# LowLevelv2.net
KiCad netlist of a schematic drawn in EAGLE
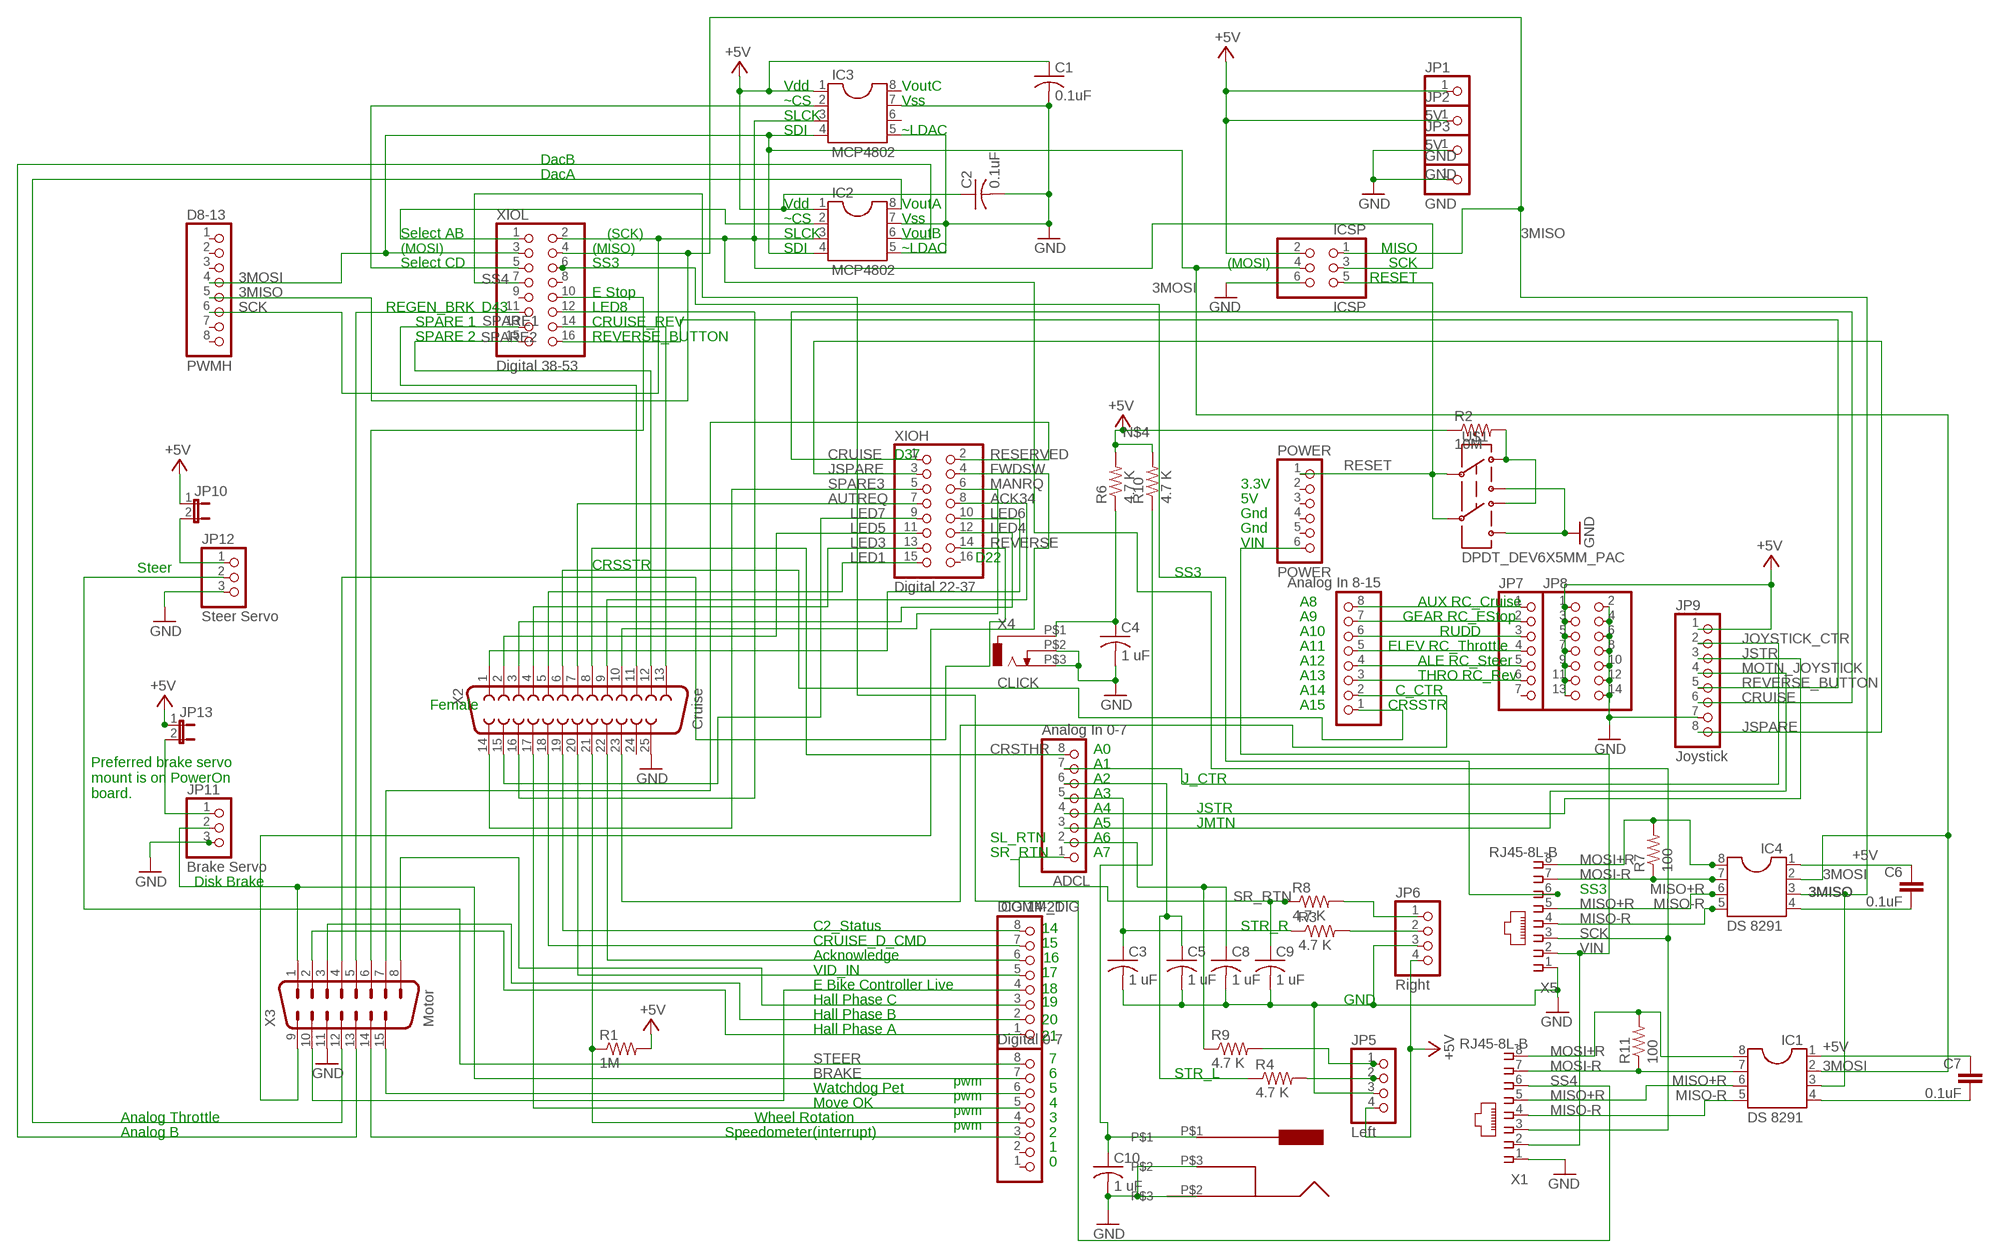
[diagram p0: schematic, sheet 1]

(export (version "E")
  (design (tool "Eeschema 10.0.6"))
  (components
    (comp (ref "ADCH")
      (value "Analog In 8-15")
      (footprint "eagle-import:1X08")
      (libsource (lib "eagle-import") (part "PINHD-1X8"))
    )
    (comp (ref "ADCL")
      (value "Analog In 0-7")
      (footprint "eagle-import:1X08")
      (libsource (lib "eagle-import") (part "PINHD-1X8"))
    )
    (comp (ref "C1")
      (value "0.1uF")
      (footprint "eagle-import:C025-025X050")
      (libsource (lib "eagle-import") (part "C-US025-025X050"))
    )
    (comp (ref "C2")
      (value "0.1uF")
      (footprint "eagle-import:C025-025X050")
      (libsource (lib "eagle-import") (part "C-US025-025X050"))
    )
    (comp (ref "C3")
      (value "1 uF")
      (footprint "eagle-import:C025-030X050")
      (libsource (lib "eagle-import") (part "C-US025-030X050"))
    )
    (comp (ref "C4")
      (value "1 uF")
      (footprint "eagle-import:C025-030X050")
      (libsource (lib "eagle-import") (part "C-US025-030X050"))
    )
    (comp (ref "C5")
      (value "1 uF")
      (footprint "eagle-import:C025-030X050")
      (libsource (lib "eagle-import") (part "C-US025-030X050"))
    )
    (comp (ref "C6")
      (value "0.1uF")
      (footprint "eagle-import:C2.5-2")
      (libsource (lib "eagle-import") (part "C2.5/2"))
    )
    (comp (ref "C7")
      (value "0.1uF")
      (footprint "eagle-import:C2.5-2")
      (libsource (lib "eagle-import") (part "C2.5/2"))
    )
    (comp (ref "C8")
      (value "1 uF")
      (footprint "eagle-import:C025-030X050")
      (libsource (lib "eagle-import") (part "C-US025-030X050"))
    )
    (comp (ref "C9")
      (value "1 uF")
      (footprint "eagle-import:C025-030X050")
      (libsource (lib "eagle-import") (part "C-US025-030X050"))
    )
    (comp (ref "C10")
      (value "1 uF")
      (footprint "eagle-import:C025-030X050")
      (libsource (lib "eagle-import") (part "C-US025-030X050"))
    )
    (comp (ref "COMM_DIG")
      (value "DIG 14-21")
      (footprint "eagle-import:1X08")
      (libsource (lib "eagle-import") (part "PINHD-1X8"))
    )
    (comp (ref "D8-13")
      (value "PWMH")
      (footprint "eagle-import:1X08")
      (libsource (lib "eagle-import") (part "PINHD-1X8"))
    )
    (comp (ref "GND")
      (value "GND")
      (footprint "eagle-import:1X01")
      (libsource (lib "eagle-import") (part "PINHD-1X1"))
    )
    (comp (ref "IC1")
      (value "DS 8291")
      (footprint "eagle-import:DIL08")
      (libsource (lib "eagle-import") (part "DIL8"))
    )
    (comp (ref "IC2")
      (value "MCP4802")
      (footprint "eagle-import:DIL08")
      (libsource (lib "eagle-import") (part "DIL8"))
    )
    (comp (ref "IC3")
      (value "MCP4802")
      (footprint "eagle-import:DIL08")
      (libsource (lib "eagle-import") (part "DIL8"))
    )
    (comp (ref "IC4")
      (value "DS 8291")
      (footprint "eagle-import:DIL08")
      (libsource (lib "eagle-import") (part "DIL8"))
    )
    (comp (ref "ICSP")
      (value "ICSP")
      (footprint "eagle-import:2X03")
      (libsource (lib "eagle-import") (part "PINHD-2X3"))
    )
    (comp (ref "JP1")
      (value "5V")
      (footprint "eagle-import:1X01")
      (libsource (lib "eagle-import") (part "PINHD-1X1"))
    )
    (comp (ref "JP2")
      (value "5V")
      (footprint "eagle-import:1X01")
      (libsource (lib "eagle-import") (part "PINHD-1X1"))
    )
    (comp (ref "JP3")
      (value "GND")
      (footprint "eagle-import:1X01")
      (libsource (lib "eagle-import") (part "PINHD-1X1"))
    )
    (comp (ref "JP5")
      (value "Left")
      (footprint "eagle-import:1X04_90")
      (libsource (lib "eagle-import") (part "PINHD-1X4/90"))
    )
    (comp (ref "JP6")
      (value "Right")
      (footprint "eagle-import:1X04_90")
      (libsource (lib "eagle-import") (part "PINHD-1X4/90"))
    )
    (comp (ref "JP7")
      (value "PINHD-1X7")
      (footprint "eagle-import:1X07")
      (libsource (lib "eagle-import") (part "PINHD-1X7"))
    )
    (comp (ref "JP8")
      (value "PINHD-2X7")
      (footprint "eagle-import:2X07")
      (libsource (lib "eagle-import") (part "PINHD-2X7"))
    )
    (comp (ref "JP9")
      (value "Joystick")
      (footprint "eagle-import:1X08_90")
      (libsource (lib "eagle-import") (part "PINHD-1X8/90"))
    )
    (comp (ref "JP10")
      (value "JP1E")
      (footprint "eagle-import:JP1")
      (libsource (lib "eagle-import") (part "JP1E"))
    )
    (comp (ref "JP11")
      (value "Brake Servo")
      (footprint "eagle-import:1X03_90")
      (libsource (lib "eagle-import") (part "PINHD-1X3/90"))
    )
    (comp (ref "JP12")
      (value "Steer Servo")
      (footprint "eagle-import:1X03_90")
      (libsource (lib "eagle-import") (part "PINHD-1X3/90"))
    )
    (comp (ref "JP13")
      (value "JP1E")
      (footprint "eagle-import:JP1")
      (libsource (lib "eagle-import") (part "JP1E"))
    )
    (comp (ref "POWER")
      (value "POWER")
      (footprint "eagle-import:1X06")
      (libsource (lib "eagle-import") (part "PINHD-1X6"))
    )
    (comp (ref "PWML")
      (value "Digital 0-7")
      (footprint "eagle-import:1X08")
      (libsource (lib "eagle-import") (part "PINHD-1X8"))
    )
    (comp (ref "R1")
      (value "1M")
      (footprint "eagle-import:0207_10")
      (libsource (lib "eagle-import") (part "R-US_0207/10"))
    )
    (comp (ref "R2")
      (value "10M")
      (footprint "eagle-import:0207_10")
      (libsource (lib "eagle-import") (part "R-US_0207/10"))
    )
    (comp (ref "R3")
      (value "4.7 K")
      (footprint "eagle-import:0207_10")
      (libsource (lib "eagle-import") (part "R-US_0207/10"))
    )
    (comp (ref "R4")
      (value "4.7 K")
      (footprint "eagle-import:0207_10")
      (libsource (lib "eagle-import") (part "R-US_0207/10"))
    )
    (comp (ref "R6")
      (value "4.7 K")
      (footprint "eagle-import:0207_10")
      (libsource (lib "eagle-import") (part "R-US_0207/10"))
    )
    (comp (ref "R7")
      (value "100")
      (footprint "eagle-import:0207_10")
      (libsource (lib "eagle-import") (part "R-US_0207/10"))
    )
    (comp (ref "R8")
      (value "4.7 K")
      (footprint "eagle-import:0207_10")
      (libsource (lib "eagle-import") (part "R-US_0207/10"))
    )
    (comp (ref "R9")
      (value "4.7 K")
      (footprint "eagle-import:0207_10")
      (libsource (lib "eagle-import") (part "R-US_0207/10"))
    )
    (comp (ref "R10")
      (value "4.7 K")
      (footprint "eagle-import:0207_10")
      (libsource (lib "eagle-import") (part "R-US_0207/10"))
    )
    (comp (ref "R11")
      (value "100")
      (footprint "eagle-import:0207_10")
      (libsource (lib "eagle-import") (part "R-US_0207/10"))
    )
    (comp (ref "U$1")
      (value "DPDT_DEV6X5MM_PAC")
      (footprint "eagle-import:NEWSWITCH2_PAC")
      (libsource (lib "eagle-import") (part "DPDT_DEV6X5MM_PAC"))
    )
    (comp (ref "U$2")
      (value "CUI_JACKTHROUGH_HOLE")
      (footprint "eagle-import:CUIJACK")
      (libsource (lib "eagle-import") (part "CUI_JACKTHROUGH_HOLE"))
    )
    (comp (ref "X1")
      (value "RJ45-8L-B")
      (footprint "eagle-import:RJ45-NO-SHIELD")
      (fields (field (name "MF") "TYCO ELECTRONICS"))
      (libsource (lib "eagle-import") (part "RJ45-8L-B"))
    )
    (comp (ref "X2")
      (value "Cruise")
      (footprint "eagle-import:F25H")
      (libsource (lib "eagle-import") (part "F25H"))
    )
    (comp (ref "X3")
      (value "Motor")
      (footprint "eagle-import:182-015-MALE")
      (libsource (lib "eagle-import") (part "M15-182"))
    )
    (comp (ref "X4")
      (value "CLICK")
      (footprint "eagle-import:ODO_JACK")
      (libsource (lib "eagle-import") (part "ODO_JACK"))
    )
    (comp (ref "X5")
      (value "RJ45-8L-B")
      (footprint "eagle-import:RJ45-NO-SHIELD")
      (fields (field (name "MF") "TYCO ELECTRONICS"))
      (libsource (lib "eagle-import") (part "RJ45-8L-B"))
    )
    (comp (ref "XIOH")
      (value "Digital 22-37")
      (footprint "eagle-import:2X08")
      (libsource (lib "eagle-import") (part "PINHD-2X8"))
    )
    (comp (ref "XIOL")
      (value "Digital 38-53")
      (footprint "eagle-import:2X08")
      (libsource (lib "eagle-import") (part "PINHD-2X8"))
    )
  )
  (nets
    (net (code "1") (name "+5V") (class "Default")
      (node (ref "C1") (pin "1") (pinfunction "1_1") (pintype "passive"))
      (node (ref "C2") (pin "1") (pinfunction "1_1") (pintype "passive"))
      (node (ref "C6") (pin "1") (pinfunction "1_1") (pintype "passive"))
      (node (ref "IC2") (pin "1") (pinfunction "1_1") (pintype "passive"))
      (node (ref "IC3") (pin "1") (pinfunction "1_1") (pintype "passive"))
      (node (ref "IC4") (pin "1") (pinfunction "1_1") (pintype "passive"))
      (node (ref "ICSP") (pin "2") (pinfunction "2_2") (pintype "passive"))
      (node (ref "JP1") (pin "1") (pinfunction "1_1") (pintype "passive"))
      (node (ref "JP10") (pin "1") (pinfunction "1_1") (pintype "passive"))
      (node (ref "JP13") (pin "1") (pinfunction "1_1") (pintype "passive"))
      (node (ref "JP2") (pin "1") (pinfunction "1_1") (pintype "passive"))
      (node (ref "JP5") (pin "4") (pinfunction "4_4") (pintype "passive"))
      (node (ref "JP6") (pin "4") (pinfunction "4_4") (pintype "passive"))
      (node (ref "JP8") (pin "1") (pinfunction "1_1") (pintype "passive"))
      (node (ref "JP8") (pin "11") (pinfunction "11_11") (pintype "passive"))
      (node (ref "JP8") (pin "13") (pinfunction "13_13") (pintype "passive"))
      (node (ref "JP8") (pin "3") (pinfunction "3_3") (pintype "passive"))
      (node (ref "JP8") (pin "5") (pinfunction "5_5") (pintype "passive"))
      (node (ref "JP8") (pin "7") (pinfunction "7_7") (pintype "passive"))
      (node (ref "JP8") (pin "9") (pinfunction "9_9") (pintype "passive"))
      (node (ref "JP9") (pin "1") (pinfunction "1_1") (pintype "passive"))
      (node (ref "R1") (pin "2") (pinfunction "2_2") (pintype "passive"))
      (node (ref "R10") (pin "2") (pinfunction "2_2") (pintype "passive"))
      (node (ref "R2") (pin "1") (pinfunction "1_1") (pintype "passive"))
      (node (ref "R6") (pin "2") (pinfunction "2_2") (pintype "passive"))
    )
    (net (code "2") (name "3MISO") (class "Default")
      (node (ref "D8-13") (pin "5") (pinfunction "5_5") (pintype "passive"))
      (node (ref "IC1") (pin "3") (pinfunction "3_3") (pintype "passive"))
      (node (ref "IC4") (pin "3") (pinfunction "3_3") (pintype "passive"))
      (node (ref "ICSP") (pin "1") (pinfunction "1_1") (pintype "passive"))
      (node (ref "XIOL") (pin "4") (pinfunction "4_4") (pintype "passive"))
    )
    (net (code "3") (name "3MOSI") (class "Default")
      (node (ref "D8-13") (pin "4") (pinfunction "4_4") (pintype "passive"))
      (node (ref "IC1") (pin "2") (pinfunction "2_2") (pintype "passive"))
      (node (ref "IC2") (pin "4") (pinfunction "4_4") (pintype "passive"))
      (node (ref "IC3") (pin "4") (pinfunction "4_4") (pintype "passive"))
      (node (ref "IC4") (pin "2") (pinfunction "2_2") (pintype "passive"))
      (node (ref "ICSP") (pin "4") (pinfunction "4_4") (pintype "passive"))
      (node (ref "XIOL") (pin "3") (pinfunction "3_3") (pintype "passive"))
    )
    (net (code "4") (name "ACK34") (class "Default")
      (node (ref "X2") (pin "9") (pinfunction "9_9") (pintype "passive"))
      (node (ref "XIOH") (pin "8") (pinfunction "8_8") (pintype "passive"))
    )
    (net (code "5") (name "AUTREQ") (class "Default")
      (node (ref "X2") (pin "7") (pinfunction "7_7") (pintype "passive"))
      (node (ref "XIOH") (pin "7") (pinfunction "7_7") (pintype "passive"))
    )
    (net (code "6") (name "BRAKE") (class "Default")
      (node (ref "JP11") (pin "2") (pinfunction "2_2") (pintype "passive"))
      (node (ref "PWML") (pin "7") (pinfunction "7_7") (pintype "passive"))
      (node (ref "X3") (pin "1") (pinfunction "1_1") (pintype "passive"))
    )
    (net (code "7") (name "CRSTHR") (class "Default")
      (node (ref "ADCL") (pin "8") (pinfunction "8_8") (pintype "passive"))
      (node (ref "X2") (pin "8") (pinfunction "8_8") (pintype "passive"))
    )
    (net (code "8") (name "CRUISE") (class "Default")
      (node (ref "JP9") (pin "6") (pinfunction "6_6") (pintype "passive"))
      (node (ref "XIOH") (pin "1") (pinfunction "1_1") (pintype "passive"))
    )
    (net (code "9") (name "CRUISE_D_CMD") (class "Default")
      (node (ref "COMM_DIG") (pin "7") (pinfunction "7_7") (pintype "passive"))
      (node (ref "X2") (pin "18") (pinfunction "18_18") (pintype "passive"))
    )
    (net (code "10") (name "CRUISE_REV") (class "Default")
      (node (ref "X2") (pin "13") (pinfunction "13_13") (pintype "passive"))
      (node (ref "XIOL") (pin "14") (pinfunction "14_14") (pintype "passive"))
    )
    (net (code "11") (name "FWDSW") (class "Default")
      (node (ref "X3") (pin "9") (pinfunction "9_9") (pintype "passive"))
      (node (ref "XIOH") (pin "4") (pinfunction "4_4") (pintype "passive"))
    )
    (net (code "12") (name "GND") (class "Default")
      (node (ref "C1") (pin "2") (pinfunction "2_2") (pintype "passive"))
      (node (ref "C10") (pin "2") (pinfunction "2_2") (pintype "passive"))
      (node (ref "C2") (pin "2") (pinfunction "2_2") (pintype "passive"))
      (node (ref "C3") (pin "2") (pinfunction "2_2") (pintype "passive"))
      (node (ref "C4") (pin "2") (pinfunction "2_2") (pintype "passive"))
      (node (ref "C5") (pin "2") (pinfunction "2_2") (pintype "passive"))
      (node (ref "C8") (pin "2") (pinfunction "2_2") (pintype "passive"))
      (node (ref "C9") (pin "2") (pinfunction "2_2") (pintype "passive"))
      (node (ref "GND") (pin "1") (pinfunction "1_1") (pintype "passive"))
      (node (ref "IC2") (pin "5") (pinfunction "5_5") (pintype "passive"))
      (node (ref "IC2") (pin "7") (pinfunction "7_7") (pintype "passive"))
      (node (ref "IC3") (pin "5") (pinfunction "5_5") (pintype "passive"))
      (node (ref "IC3") (pin "7") (pinfunction "7_7") (pintype "passive"))
      (node (ref "ICSP") (pin "6") (pinfunction "6_6") (pintype "passive"))
      (node (ref "JP11") (pin "3") (pinfunction "3_3") (pintype "passive"))
      (node (ref "JP12") (pin "3") (pinfunction "3_3") (pintype "passive"))
      (node (ref "JP3") (pin "1") (pinfunction "1_1") (pintype "passive"))
      (node (ref "JP5") (pin "3") (pinfunction "3_3") (pintype "passive"))
      (node (ref "JP6") (pin "3") (pinfunction "3_3") (pintype "passive"))
      (node (ref "JP8") (pin "10") (pinfunction "10_10") (pintype "passive"))
      (node (ref "JP8") (pin "12") (pinfunction "12_12") (pintype "passive"))
      (node (ref "JP8") (pin "14") (pinfunction "14_14") (pintype "passive"))
      (node (ref "JP8") (pin "2") (pinfunction "2_2") (pintype "passive"))
      (node (ref "JP8") (pin "4") (pinfunction "4_4") (pintype "passive"))
      (node (ref "JP8") (pin "6") (pinfunction "6_6") (pintype "passive"))
      (node (ref "JP8") (pin "8") (pinfunction "8_8") (pintype "passive"))
      (node (ref "JP9") (pin "7") (pinfunction "7_7") (pintype "passive"))
      (node (ref "U$1") (pin "PIN3") (pinfunction "3_PIN3") (pintype "bidirectional"))
      (node (ref "U$1") (pin "PIN6") (pinfunction "6_PIN6") (pintype "bidirectional"))
      (node (ref "U$2") (pin "P$2") (pinfunction "P$3_P$2") (pintype "bidirectional"))
      (node (ref "U$2") (pin "P$3") (pinfunction "P$2_P$3") (pintype "bidirectional"))
      (node (ref "X1") (pin "1") (pinfunction "1_1") (pintype "passive"))
      (node (ref "X2") (pin "25") (pinfunction "25_25") (pintype "passive"))
      (node (ref "X3") (pin "11") (pinfunction "11_11") (pintype "passive"))
      (node (ref "X4") (pin "P$2") (pinfunction "2_P$2") (pintype "passive"))
      (node (ref "X4") (pin "P$3") (pinfunction "3_P$3") (pintype "passive"))
      (node (ref "X5") (pin "1") (pinfunction "1_1") (pintype "passive"))
    )
    (net (code "13") (name "JOYSTICK_CTR") (class "Default")
      (node (ref "ADCL") (pin "7") (pinfunction "7_7") (pintype "passive"))
      (node (ref "JP9") (pin "2") (pinfunction "2_2") (pintype "passive"))
    )
    (net (code "14") (name "JSPARE") (class "Default")
      (node (ref "JP9") (pin "8") (pinfunction "8_8") (pintype "passive"))
      (node (ref "XIOH") (pin "3") (pinfunction "3_3") (pintype "passive"))
    )
    (net (code "15") (name "JSTR") (class "Default")
      (node (ref "ADCL") (pin "4") (pinfunction "4_4") (pintype "passive"))
      (node (ref "JP9") (pin "3") (pinfunction "3_3") (pintype "passive"))
    )
    (net (code "16") (name "LED1") (class "Default")
      (node (ref "X2") (pin "5") (pinfunction "5_5") (pintype "passive"))
      (node (ref "XIOH") (pin "15") (pinfunction "15_15") (pintype "passive"))
    )
    (net (code "17") (name "LED3") (class "Default")
      (node (ref "X2") (pin "4") (pinfunction "4_4") (pintype "passive"))
      (node (ref "XIOH") (pin "13") (pinfunction "13_13") (pintype "passive"))
    )
    (net (code "18") (name "LED4") (class "Default")
      (node (ref "X2") (pin "3") (pinfunction "3_3") (pintype "passive"))
      (node (ref "XIOH") (pin "12") (pinfunction "12_12") (pintype "passive"))
    )
    (net (code "19") (name "LED5") (class "Default")
      (node (ref "X2") (pin "2") (pinfunction "2_2") (pintype "passive"))
      (node (ref "XIOH") (pin "11") (pinfunction "11_11") (pintype "passive"))
    )
    (net (code "20") (name "LED6") (class "Default")
      (node (ref "X2") (pin "1") (pinfunction "1_1") (pintype "passive"))
      (node (ref "XIOH") (pin "10") (pinfunction "10_10") (pintype "passive"))
    )
    (net (code "21") (name "LED7") (class "Default")
      (node (ref "X2") (pin "15") (pinfunction "15_15") (pintype "passive"))
      (node (ref "XIOH") (pin "9") (pinfunction "9_9") (pintype "passive"))
    )
    (net (code "22") (name "LED8") (class "Default")
      (node (ref "X2") (pin "16") (pinfunction "16_16") (pintype "passive"))
      (node (ref "XIOL") (pin "12") (pinfunction "12_12") (pintype "passive"))
    )
    (net (code "23") (name "MANRQ") (class "Default")
      (node (ref "X2") (pin "10") (pinfunction "10_10") (pintype "passive"))
      (node (ref "XIOH") (pin "6") (pinfunction "6_6") (pintype "passive"))
    )
    (net (code "24") (name "MISO+R") (class "Default")
      (node (ref "IC1") (pin "6") (pinfunction "6_6") (pintype "passive"))
      (node (ref "IC4") (pin "6") (pinfunction "6_6") (pintype "passive"))
      (node (ref "X1") (pin "5") (pinfunction "5_5") (pintype "passive"))
      (node (ref "X5") (pin "5") (pinfunction "5_5") (pintype "passive"))
    )
    (net (code "25") (name "MISO-R") (class "Default")
      (node (ref "IC1") (pin "5") (pinfunction "5_5") (pintype "passive"))
      (node (ref "IC4") (pin "5") (pinfunction "5_5") (pintype "passive"))
      (node (ref "X1") (pin "4") (pinfunction "4_4") (pintype "passive"))
      (node (ref "X5") (pin "4") (pinfunction "4_4") (pintype "passive"))
    )
    (net (code "26") (name "MOSI+R") (class "Default")
      (node (ref "IC1") (pin "8") (pinfunction "8_8") (pintype "passive"))
      (node (ref "IC4") (pin "8") (pinfunction "8_8") (pintype "passive"))
      (node (ref "R11") (pin "2") (pinfunction "2_2") (pintype "passive"))
      (node (ref "R7") (pin "2") (pinfunction "2_2") (pintype "passive"))
      (node (ref "X1") (pin "8") (pinfunction "8_8") (pintype "passive"))
      (node (ref "X5") (pin "8") (pinfunction "8_8") (pintype "passive"))
    )
    (net (code "27") (name "MOSI-R") (class "Default")
      (node (ref "IC1") (pin "7") (pinfunction "7_7") (pintype "passive"))
      (node (ref "IC4") (pin "7") (pinfunction "7_7") (pintype "passive"))
      (node (ref "R11") (pin "1") (pinfunction "1_1") (pintype "passive"))
      (node (ref "R7") (pin "1") (pinfunction "1_1") (pintype "passive"))
      (node (ref "X1") (pin "7") (pinfunction "7_7") (pintype "passive"))
      (node (ref "X5") (pin "7") (pinfunction "7_7") (pintype "passive"))
    )
    (net (code "28") (name "MOTN_JOYSTICK") (class "Default")
      (node (ref "ADCL") (pin "3") (pinfunction "3_3") (pintype "passive"))
      (node (ref "JP9") (pin "4") (pinfunction "4_4") (pintype "passive"))
    )
    (net (code "29") (name "N$4") (class "Default")
      (node (ref "C4") (pin "1") (pinfunction "1_1") (pintype "passive"))
      (node (ref "R6") (pin "1") (pinfunction "1_1") (pintype "passive"))
      (node (ref "X4") (pin "P$1") (pinfunction "1_P$1") (pintype "passive"))
    )
    (net (code "30") (name "Net-(ADCH-Pad1)") (class "Default")
      (node (ref "ADCH") (pin "1") (pinfunction "1_1") (pintype "passive"))
      (node (ref "X2") (pin "6") (pinfunction "6_6") (pintype "passive"))
    )
    (net (code "31") (name "Net-(ADCH-Pad2)") (class "Default")
      (node (ref "ADCH") (pin "2") (pinfunction "2_2") (pintype "passive"))
      (node (ref "X2") (pin "23") (pinfunction "23_23") (pintype "passive"))
    )
    (net (code "32") (name "Net-(ADCH-Pad3)") (class "Default")
      (node (ref "ADCH") (pin "3") (pinfunction "3_3") (pintype "passive"))
      (node (ref "JP7") (pin "6") (pinfunction "6_6") (pintype "passive"))
    )
    (net (code "33") (name "Net-(ADCH-Pad4)") (class "Default")
      (node (ref "ADCH") (pin "4") (pinfunction "4_4") (pintype "passive"))
      (node (ref "JP7") (pin "5") (pinfunction "5_5") (pintype "passive"))
    )
    (net (code "34") (name "Net-(ADCH-Pad5)") (class "Default")
      (node (ref "ADCH") (pin "5") (pinfunction "5_5") (pintype "passive"))
      (node (ref "JP7") (pin "4") (pinfunction "4_4") (pintype "passive"))
    )
    (net (code "35") (name "Net-(ADCH-Pad6)") (class "Default")
      (node (ref "ADCH") (pin "6") (pinfunction "6_6") (pintype "passive"))
      (node (ref "JP7") (pin "3") (pinfunction "3_3") (pintype "passive"))
    )
    (net (code "36") (name "Net-(ADCH-Pad7)") (class "Default")
      (node (ref "ADCH") (pin "7") (pinfunction "7_7") (pintype "passive"))
      (node (ref "JP7") (pin "2") (pinfunction "2_2") (pintype "passive"))
    )
    (net (code "37") (name "Net-(ADCH-Pad8)") (class "Default")
      (node (ref "ADCH") (pin "8") (pinfunction "8_8") (pintype "passive"))
      (node (ref "JP7") (pin "1") (pinfunction "1_1") (pintype "passive"))
    )
    (net (code "38") (name "Net-(ADCL-Pad2)") (class "Default")
      (node (ref "ADCL") (pin "2") (pinfunction "2_2") (pintype "passive"))
      (node (ref "C8") (pin "1") (pinfunction "1_1") (pintype "passive"))
      (node (ref "R9") (pin "1") (pinfunction "1_1") (pintype "passive"))
    )
    (net (code "39") (name "Net-(ADCL-Pad5)") (class "Default")
      (node (ref "ADCL") (pin "5") (pinfunction "5_5") (pintype "passive"))
      (node (ref "C3") (pin "1") (pinfunction "1_1") (pintype "passive"))
      (node (ref "R3") (pin "1") (pinfunction "1_1") (pintype "passive"))
    )
    (net (code "40") (name "Net-(ADCL-Pad6)") (class "Default")
      (node (ref "ADCL") (pin "6") (pinfunction "6_6") (pintype "passive"))
      (node (ref "C5") (pin "1") (pinfunction "1_1") (pintype "passive"))
      (node (ref "R4") (pin "1") (pinfunction "1_1") (pintype "passive"))
    )
    (net (code "41") (name "Net-(C6-Pad2)") (class "Default")
      (node (ref "C6") (pin "2") (pinfunction "2_2") (pintype "passive"))
      (node (ref "IC4") (pin "4") (pinfunction "4_4") (pintype "passive"))
    )
    (net (code "42") (name "Net-(C7-Pad1)") (class "Default")
      (node (ref "C7") (pin "1") (pinfunction "1_1") (pintype "passive"))
      (node (ref "IC1") (pin "1") (pinfunction "1_1") (pintype "passive"))
    )
    (net (code "43") (name "Net-(C7-Pad2)") (class "Default")
      (node (ref "C7") (pin "2") (pinfunction "2_2") (pintype "passive"))
      (node (ref "IC1") (pin "4") (pinfunction "4_4") (pintype "passive"))
    )
    (net (code "44") (name "Net-(C10-Pad1)") (class "Default")
      (node (ref "C10") (pin "1") (pinfunction "1_1") (pintype "passive"))
      (node (ref "R10") (pin "1") (pinfunction "1_1") (pintype "passive"))
      (node (ref "U$2") (pin "P$1") (pinfunction "P$1_P$1") (pintype "bidirectional"))
    )
    (net (code "45") (name "Net-(COMM_DIG-Pad1)") (class "Default")
      (node (ref "COMM_DIG") (pin "1") (pinfunction "1_1") (pintype "passive"))
      (node (ref "X3") (pin "2") (pinfunction "2_2") (pintype "passive"))
    )
    (net (code "46") (name "Net-(COMM_DIG-Pad2)") (class "Default")
      (node (ref "COMM_DIG") (pin "2") (pinfunction "2_2") (pintype "passive"))
      (node (ref "X3") (pin "3") (pinfunction "3_3") (pintype "passive"))
    )
    (net (code "47") (name "Net-(COMM_DIG-Pad3)") (class "Default")
      (node (ref "COMM_DIG") (pin "3") (pinfunction "3_3") (pintype "passive"))
      (node (ref "X3") (pin "8") (pinfunction "8_8") (pintype "passive"))
    )
    (net (code "48") (name "Net-(COMM_DIG-Pad4)") (class "Default")
      (node (ref "COMM_DIG") (pin "4") (pinfunction "4_4") (pintype "passive"))
      (node (ref "X3") (pin "10") (pinfunction "10_10") (pintype "passive"))
    )
    (net (code "49") (name "Net-(COMM_DIG-Pad5)") (class "Default")
      (node (ref "COMM_DIG") (pin "5") (pinfunction "5_5") (pintype "passive"))
      (node (ref "X2") (pin "20") (pinfunction "20_20") (pintype "passive"))
    )
    (net (code "50") (name "Net-(COMM_DIG-Pad6)") (class "Default")
      (node (ref "COMM_DIG") (pin "6") (pinfunction "6_6") (pintype "passive"))
      (node (ref "X2") (pin "22") (pinfunction "22_22") (pintype "passive"))
    )
    (net (code "51") (name "Net-(COMM_DIG-Pad8)") (class "Default")
      (node (ref "COMM_DIG") (pin "8") (pinfunction "8_8") (pintype "passive"))
      (node (ref "X2") (pin "19") (pinfunction "19_19") (pintype "passive"))
    )
    (net (code "52") (name "Net-(IC2-Pad2)") (class "Default")
      (node (ref "IC2") (pin "2") (pinfunction "2_2") (pintype "passive"))
      (node (ref "XIOL") (pin "1") (pinfunction "1_1") (pintype "passive"))
    )
    (net (code "53") (name "Net-(IC2-Pad6)") (class "Default")
      (node (ref "IC2") (pin "6") (pinfunction "6_6") (pintype "passive"))
      (node (ref "X3") (pin "13") (pinfunction "13_13") (pintype "passive"))
    )
    (net (code "54") (name "Net-(IC2-Pad8)") (class "Default")
      (node (ref "IC2") (pin "8") (pinfunction "8_8") (pintype "passive"))
      (node (ref "X3") (pin "12") (pinfunction "12_12") (pintype "passive"))
    )
    (net (code "55") (name "Net-(IC3-Pad2)") (class "Default")
      (node (ref "IC3") (pin "2") (pinfunction "2_2") (pintype "passive"))
      (node (ref "XIOL") (pin "5") (pinfunction "5_5") (pintype "passive"))
    )
    (net (code "56") (name "Net-(JP5-Pad1)") (class "Default")
      (node (ref "JP5") (pin "1") (pinfunction "1_1") (pintype "passive"))
      (node (ref "R9") (pin "2") (pinfunction "2_2") (pintype "passive"))
    )
    (net (code "57") (name "Net-(JP5-Pad2)") (class "Default")
      (node (ref "JP5") (pin "2") (pinfunction "2_2") (pintype "passive"))
      (node (ref "R4") (pin "2") (pinfunction "2_2") (pintype "passive"))
    )
    (net (code "58") (name "Net-(JP6-Pad1)") (class "Default")
      (node (ref "JP6") (pin "1") (pinfunction "1_1") (pintype "passive"))
      (node (ref "R8") (pin "2") (pinfunction "2_2") (pintype "passive"))
    )
    (net (code "59") (name "Net-(JP6-Pad2)") (class "Default")
      (node (ref "JP6") (pin "2") (pinfunction "2_2") (pintype "passive"))
      (node (ref "R3") (pin "2") (pinfunction "2_2") (pintype "passive"))
    )
    (net (code "60") (name "Net-(JP10-Pad2)") (class "Default")
      (node (ref "JP10") (pin "2") (pinfunction "2_2") (pintype "passive"))
      (node (ref "JP12") (pin "1") (pinfunction "1_1") (pintype "passive"))
    )
    (net (code "61") (name "Net-(JP11-Pad1)") (class "Default")
      (node (ref "JP11") (pin "1") (pinfunction "1_1") (pintype "passive"))
      (node (ref "JP13") (pin "2") (pinfunction "2_2") (pintype "passive"))
    )
    (net (code "62") (name "Net-(PWML-Pad3)") (class "Default")
      (node (ref "PWML") (pin "3") (pinfunction "3_3") (pintype "passive"))
      (node (ref "X3") (pin "14") (pinfunction "14_14") (pintype "passive"))
    )
    (net (code "63") (name "Net-(PWML-Pad4)") (class "Default")
      (node (ref "PWML") (pin "4") (pinfunction "4_4") (pintype "passive"))
      (node (ref "R1") (pin "1") (pinfunction "1_1") (pintype "passive"))
      (node (ref "X2") (pin "21") (pinfunction "21_21") (pintype "passive"))
    )
    (net (code "64") (name "Net-(PWML-Pad5)") (class "Default")
      (node (ref "PWML") (pin "5") (pinfunction "5_5") (pintype "passive"))
      (node (ref "X2") (pin "17") (pinfunction "17_17") (pintype "passive"))
    )
    (net (code "65") (name "Net-(PWML-Pad6)") (class "Default")
      (node (ref "PWML") (pin "6") (pinfunction "6_6") (pintype "passive"))
      (node (ref "X3") (pin "15") (pinfunction "15_15") (pintype "passive"))
    )
    (net (code "66") (name "Net-(U$1-1)") (class "Default")
      (node (ref "R2") (pin "2") (pinfunction "2_2") (pintype "passive"))
      (node (ref "U$1") (pin "PIN1") (pinfunction "1_PIN1") (pintype "bidirectional"))
      (node (ref "U$1") (pin "PIN4") (pinfunction "4_PIN4") (pintype "bidirectional"))
    )
    (net (code "67") (name "Net-(X3-Pad5)") (class "Default")
      (node (ref "X3") (pin "5") (pinfunction "5_5") (pintype "passive"))
      (node (ref "XIOL") (pin "11") (pinfunction "11_11") (pintype "passive"))
    )
    (net (code "68") (name "Net-(X3-Pad6)") (class "Default")
      (node (ref "X3") (pin "6") (pinfunction "6_6") (pintype "passive"))
      (node (ref "XIOL") (pin "10") (pinfunction "10_10") (pintype "passive"))
    )
    (net (code "69") (name "Net-(X5-Pad6)") (class "Default")
      (node (ref "X5") (pin "6") (pinfunction "6_6") (pintype "passive"))
      (node (ref "XIOL") (pin "6") (pinfunction "6_6") (pintype "passive"))
    )
    (net (code "70") (name "RESERVED") (class "Default")
      (node (ref "X3") (pin "7") (pinfunction "7_7") (pintype "passive"))
      (node (ref "XIOH") (pin "2") (pinfunction "2_2") (pintype "passive"))
    )
    (net (code "71") (name "RESET") (class "Default")
      (node (ref "ICSP") (pin "5") (pinfunction "5_5") (pintype "passive"))
      (node (ref "POWER") (pin "1") (pinfunction "1_1") (pintype "passive"))
      (node (ref "U$1") (pin "PIN2") (pinfunction "2_PIN2") (pintype "bidirectional"))
      (node (ref "U$1") (pin "PIN5") (pinfunction "5_PIN5") (pintype "bidirectional"))
    )
    (net (code "72") (name "REVERSE") (class "Default")
      (node (ref "X3") (pin "4") (pinfunction "4_4") (pintype "passive"))
      (node (ref "XIOH") (pin "14") (pinfunction "14_14") (pintype "passive"))
    )
    (net (code "73") (name "REVERSE_BUTTON") (class "Default")
      (node (ref "JP9") (pin "5") (pinfunction "5_5") (pintype "passive"))
      (node (ref "XIOL") (pin "16") (pinfunction "16_16") (pintype "passive"))
    )
    (net (code "74") (name "SCK") (class "Default")
      (node (ref "D8-13") (pin "6") (pinfunction "6_6") (pintype "passive"))
      (node (ref "IC2") (pin "3") (pinfunction "3_3") (pintype "passive"))
      (node (ref "IC3") (pin "3") (pinfunction "3_3") (pintype "passive"))
      (node (ref "ICSP") (pin "3") (pinfunction "3_3") (pintype "passive"))
      (node (ref "X1") (pin "3") (pinfunction "3_3") (pintype "passive"))
      (node (ref "X5") (pin "3") (pinfunction "3_3") (pintype "passive"))
      (node (ref "XIOL") (pin "2") (pinfunction "2_2") (pintype "passive"))
    )
    (net (code "75") (name "SPARE1") (class "Default")
      (node (ref "X2") (pin "11") (pinfunction "11_11") (pintype "passive"))
      (node (ref "XIOL") (pin "13") (pinfunction "13_13") (pintype "passive"))
    )
    (net (code "76") (name "SPARE2") (class "Default")
      (node (ref "X2") (pin "12") (pinfunction "12_12") (pintype "passive"))
      (node (ref "XIOL") (pin "15") (pinfunction "15_15") (pintype "passive"))
    )
    (net (code "77") (name "SPARE3") (class "Default")
      (node (ref "X2") (pin "14") (pinfunction "14_14") (pintype "passive"))
      (node (ref "XIOH") (pin "5") (pinfunction "5_5") (pintype "passive"))
    )
    (net (code "78") (name "SR_RTN") (class "Default")
      (node (ref "ADCL") (pin "1") (pinfunction "1_1") (pintype "passive"))
      (node (ref "C9") (pin "1") (pinfunction "1_1") (pintype "passive"))
      (node (ref "R8") (pin "1") (pinfunction "1_1") (pintype "passive"))
    )
    (net (code "79") (name "SS4") (class "Default")
      (node (ref "X1") (pin "6") (pinfunction "6_6") (pintype "passive"))
      (node (ref "XIOL") (pin "7") (pinfunction "7_7") (pintype "passive"))
    )
    (net (code "80") (name "STEER") (class "Default")
      (node (ref "JP12") (pin "2") (pinfunction "2_2") (pintype "passive"))
      (node (ref "PWML") (pin "8") (pinfunction "8_8") (pintype "passive"))
    )
    (net (code "81") (name "VIN") (class "Default")
      (node (ref "POWER") (pin "6") (pinfunction "6_6") (pintype "passive"))
      (node (ref "X1") (pin "2") (pinfunction "2_2") (pintype "passive"))
      (node (ref "X5") (pin "2") (pinfunction "2_2") (pintype "passive"))
    )
    (net (code "82") (name "unconnected-(D8-13-Pad1)") (class "Default")
      (node (ref "D8-13") (pin "1") (pinfunction "1_1") (pintype "passive"))
    )
    (net (code "83") (name "unconnected-(D8-13-Pad2)") (class "Default")
      (node (ref "D8-13") (pin "2") (pinfunction "2_2") (pintype "passive"))
    )
    (net (code "84") (name "unconnected-(D8-13-Pad3)") (class "Default")
      (node (ref "D8-13") (pin "3") (pinfunction "3_3") (pintype "passive"))
    )
    (net (code "85") (name "unconnected-(D8-13-Pad7)") (class "Default")
      (node (ref "D8-13") (pin "7") (pinfunction "7_7") (pintype "passive"))
    )
    (net (code "86") (name "unconnected-(D8-13-Pad8)") (class "Default")
      (node (ref "D8-13") (pin "8") (pinfunction "8_8") (pintype "passive"))
    )
    (net (code "87") (name "unconnected-(IC3-Pad6)") (class "Default")
      (node (ref "IC3") (pin "6") (pinfunction "6_6") (pintype "passive"))
    )
    (net (code "88") (name "unconnected-(IC3-Pad8)") (class "Default")
      (node (ref "IC3") (pin "8") (pinfunction "8_8") (pintype "passive"))
    )
    (net (code "89") (name "unconnected-(JP7-Pad7)") (class "Default")
      (node (ref "JP7") (pin "7") (pinfunction "7_7") (pintype "passive"))
    )
    (net (code "90") (name "unconnected-(POWER-Pad2)") (class "Default")
      (node (ref "POWER") (pin "2") (pinfunction "2_2") (pintype "passive"))
    )
    (net (code "91") (name "unconnected-(POWER-Pad3)") (class "Default")
      (node (ref "POWER") (pin "3") (pinfunction "3_3") (pintype "passive"))
    )
    (net (code "92") (name "unconnected-(POWER-Pad4)") (class "Default")
      (node (ref "POWER") (pin "4") (pinfunction "4_4") (pintype "passive"))
    )
    (net (code "93") (name "unconnected-(POWER-Pad5)") (class "Default")
      (node (ref "POWER") (pin "5") (pinfunction "5_5") (pintype "passive"))
    )
    (net (code "94") (name "unconnected-(PWML-Pad1)") (class "Default")
      (node (ref "PWML") (pin "1") (pinfunction "1_1") (pintype "passive"))
    )
    (net (code "95") (name "unconnected-(PWML-Pad2)") (class "Default")
      (node (ref "PWML") (pin "2") (pinfunction "2_2") (pintype "passive"))
    )
    (net (code "96") (name "unconnected-(X2-Pad24)") (class "Default")
      (node (ref "X2") (pin "24") (pinfunction "24_24") (pintype "passive"))
    )
    (net (code "97") (name "unconnected-(XIOH-Pad16)") (class "Default")
      (node (ref "XIOH") (pin "16") (pinfunction "16_16") (pintype "passive"))
    )
    (net (code "98") (name "unconnected-(XIOL-Pad8)") (class "Default")
      (node (ref "XIOL") (pin "8") (pinfunction "8_8") (pintype "passive"))
    )
    (net (code "99") (name "unconnected-(XIOL-Pad9)") (class "Default")
      (node (ref "XIOL") (pin "9") (pinfunction "9_9") (pintype "passive"))
    )
  )
)
